# spinac.net
KiCad netlist of a schematic drawn in EAGLE
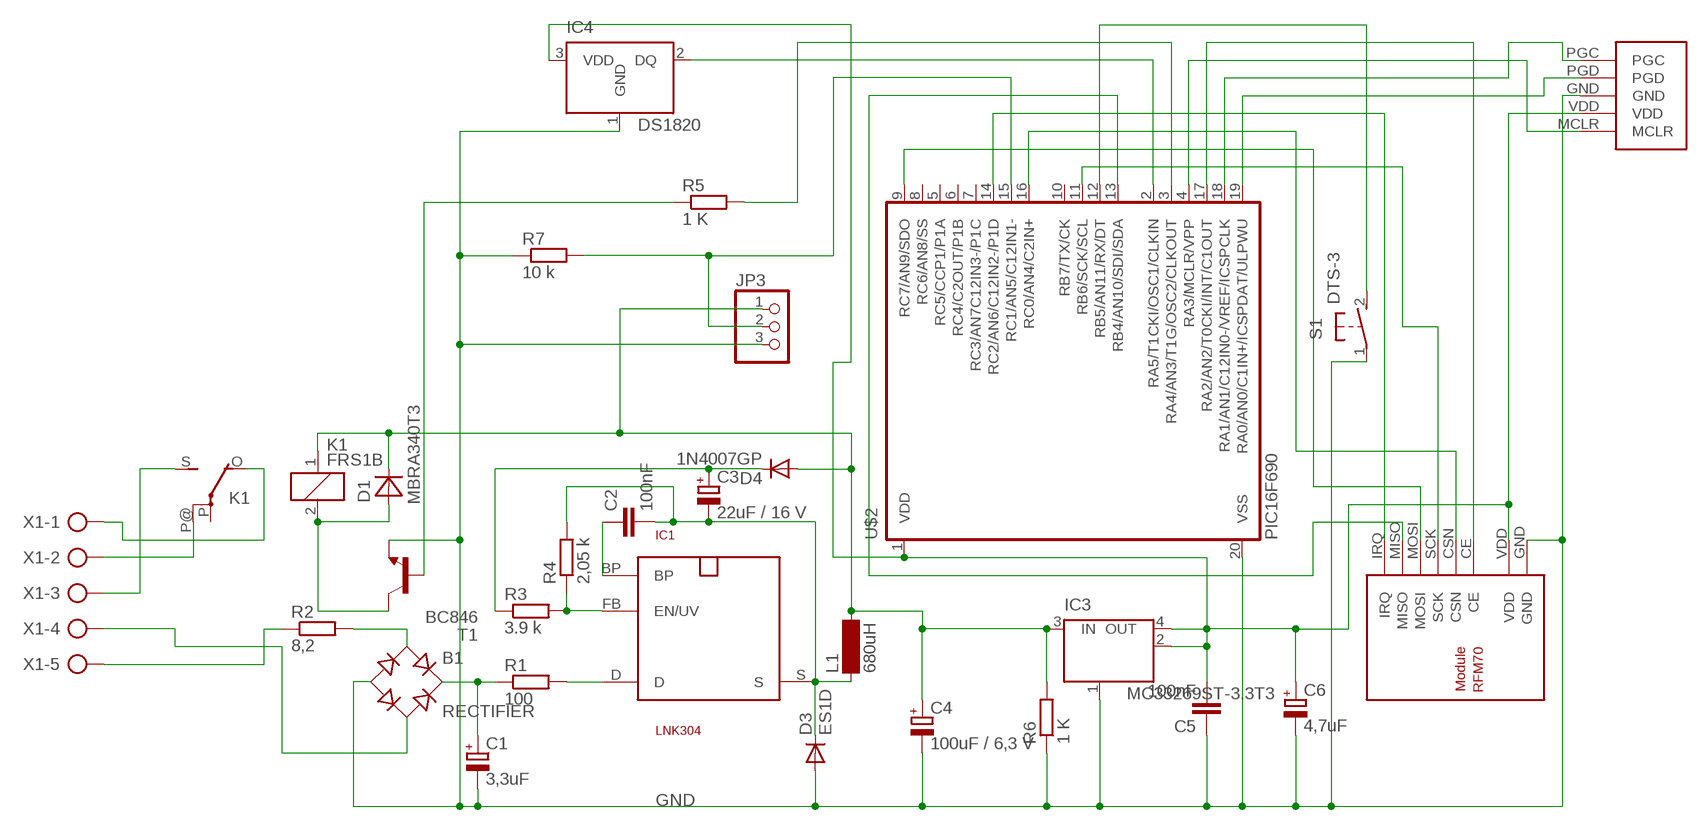
[diagram p0: schematic, sheet 1]

(export (version "E")
  (design (tool "Eeschema 10.0.6"))
  (components
    (comp (ref "B1")
      (value "RECTIFIER")
      (footprint "eagle-import:TO-269AA")
      (libsource (lib "eagle-import") (part "RECTIFIER-S40"))
    )
    (comp (ref "C1")
      (value "3,3uF")
      (footprint "eagle-import:E5-10,5")
      (libsource (lib "eagle-import") (part "CPOL-EUE5-10.5"))
    )
    (comp (ref "C2")
      (value "100nF")
      (footprint "eagle-import:C2012")
      (libsource (lib "eagle-import") (part "C-EUC2012"))
    )
    (comp (ref "C3")
      (value "22uF / 16 V")
      (footprint "eagle-import:SMC_C")
      (libsource (lib "eagle-import") (part "CPOL-EUSMCC"))
    )
    (comp (ref "C4")
      (value "100uF / 6,3 V")
      (footprint "eagle-import:E2,5-5")
      (libsource (lib "eagle-import") (part "CPOL-EUE2.5-5"))
    )
    (comp (ref "C5")
      (value "100nF")
      (footprint "eagle-import:C2012")
      (libsource (lib "eagle-import") (part "C-EUC2012"))
    )
    (comp (ref "C6")
      (value "4,7uF")
      (footprint "eagle-import:SMC_A")
      (libsource (lib "eagle-import") (part "CPOL-EUSMCA"))
    )
    (comp (ref "D1")
      (value "MBRA340T3")
      (footprint "eagle-import:SMA")
      (libsource (lib "eagle-import") (part "MBRA340T3"))
    )
    (comp (ref "D3")
      (value "ES1D")
      (footprint "eagle-import:DO214AC")
      (libsource (lib "eagle-import") (part "DIODE-DO214AC"))
    )
    (comp (ref "D4")
      (value "1N4007GP")
      (footprint "eagle-import:DO214AA")
      (libsource (lib "eagle-import") (part "DIODE-DO214AA"))
    )
    (comp (ref "IC1")
      (value "LNK304")
      (footprint "eagle-import:SO-8C")
      (libsource (lib "eagle-import") (part "SO-8C"))
    )
    (comp (ref "IC3")
      (value "MC33269ST-3.3T3")
      (footprint "eagle-import:SOT223")
      (libsource (lib "eagle-import") (part "MC33269ST-3.3T3"))
    )
    (comp (ref "IC4")
      (value "DS1820")
      (footprint "eagle-import:TO-92")
      (libsource (lib "eagle-import") (part "DS1820"))
    )
    (comp (ref "JP3")
      (value "PINHD-1X3")
      (footprint "eagle-import:1X03")
      (libsource (lib "eagle-import") (part "PINHD-1X3"))
    )
    (comp (ref "K1")
      (value "FRS1B")
      (footprint "eagle-import:FRS1B")
      (libsource (lib "eagle-import") (part "FRS1B"))
    )
    (comp (ref "L1")
      (value "680uH")
      (footprint "eagle-import:BS11")
      (libsource (lib "eagle-import") (part "BS11"))
    )
    (comp (ref "R1")
      (value "100")
      (footprint "eagle-import:R2512W")
      (libsource (lib "eagle-import") (part "R-EU_R2512W"))
    )
    (comp (ref "R2")
      (value "8,2")
      (footprint "eagle-import:0411_12")
      (libsource (lib "eagle-import") (part "R-EU_0411/12"))
    )
    (comp (ref "R3")
      (value "3.9 k")
      (footprint "eagle-import:M2012")
      (libsource (lib "eagle-import") (part "R-EU_M2012"))
    )
    (comp (ref "R4")
      (value "2,05 k")
      (footprint "eagle-import:M2012")
      (libsource (lib "eagle-import") (part "R-EU_M2012"))
    )
    (comp (ref "R5")
      (value "1 K")
      (footprint "eagle-import:M2012")
      (libsource (lib "eagle-import") (part "R-EU_M2012"))
    )
    (comp (ref "R6")
      (value "1 K")
      (footprint "eagle-import:M2012")
      (libsource (lib "eagle-import") (part "R-EU_M2012"))
    )
    (comp (ref "R7")
      (value "10 k")
      (footprint "eagle-import:M2012")
      (libsource (lib "eagle-import") (part "R-EU_M2012"))
    )
    (comp (ref "S1")
      (value "DTS-3")
      (footprint "eagle-import:DTS-3")
      (libsource (lib "eagle-import") (part "DTS-3"))
    )
    (comp (ref "T1")
      (value "BC846")
      (footprint "eagle-import:SOT23")
      (libsource (lib "eagle-import") (part "BC846"))
    )
    (comp (ref "U$1")
      (value "RFM70")
      (footprint "eagle-import:RFM70")
      (libsource (lib "eagle-import") (part "RFM70"))
    )
    (comp (ref "U$2")
      (value "PIC16F690")
      (footprint "eagle-import:SSOP20")
      (libsource (lib "eagle-import") (part "PIC16F690"))
    )
    (comp (ref "U$3")
      (value "PROGRAMMINGHEADERDIP")
      (footprint "eagle-import:PROGHEADER")
      (libsource (lib "eagle-import") (part "PROGRAMMINGHEADERDIP"))
    )
    (comp (ref "X1")
      (value "AK500/5")
      (footprint "eagle-import:AK500_5")
      (libsource (lib "eagle-import") (part "AK500/5"))
    )
  )
  (nets
    (net (code "1") (name "/GND") (class "Default")
      (node (ref "B1") (pin "-") (pinfunction "-_-") (pintype "passive"))
      (node (ref "C1") (pin "-") (pinfunction "-_-") (pintype "passive"))
      (node (ref "C4") (pin "-") (pinfunction "-_-") (pintype "passive"))
      (node (ref "C5") (pin "1") (pinfunction "1_1") (pintype "passive"))
      (node (ref "C6") (pin "-") (pinfunction "-_-") (pintype "passive"))
      (node (ref "D3") (pin "A") (pinfunction "A_A") (pintype "passive"))
      (node (ref "IC3") (pin "1") (pinfunction "GND/ADJ_1") (pintype "input"))
      (node (ref "IC4") (pin "1") (pinfunction "GND_1") (pintype "power_in"))
      (node (ref "JP3") (pin "3") (pinfunction "3_3") (pintype "passive"))
      (node (ref "R6") (pin "1") (pinfunction "1_1") (pintype "passive"))
      (node (ref "R7") (pin "1") (pinfunction "1_1") (pintype "passive"))
      (node (ref "S1") (pin "1") (pinfunction "1_1") (pintype "passive"))
      (node (ref "T1") (pin "2") (pinfunction "E_2") (pintype "passive"))
      (node (ref "U$1") (pin "GND") (pinfunction "GND_GND") (pintype "power_in"))
      (node (ref "U$2") (pin "20") (pinfunction "VSS_20") (pintype "power_in"))
      (node (ref "U$3") (pin "GND") (pinfunction "GND_GND") (pintype "power_in"))
    )
    (net (code "2") (name "Net-(B1-Pad+)") (class "Default")
      (node (ref "B1") (pin "+") (pinfunction "+_+") (pintype "passive"))
      (node (ref "C1") (pin "+") (pinfunction "+_+") (pintype "passive"))
      (node (ref "R1") (pin "1") (pinfunction "1_1") (pintype "passive"))
    )
    (net (code "3") (name "Net-(B1-PadAC1)") (class "Default")
      (node (ref "B1") (pin "AC1") (pinfunction "AC1_AC1") (pintype "passive"))
      (node (ref "R2") (pin "2") (pinfunction "2_2") (pintype "passive"))
    )
    (net (code "4") (name "Net-(C2-Pad1)") (class "Default")
      (node (ref "C2") (pin "1") (pinfunction "1_1") (pintype "passive"))
      (node (ref "IC1") (pin "BP") (pinfunction "BP_BP") (pintype "passive"))
    )
    (net (code "5") (name "Net-(C2-Pad2)") (class "Default")
      (node (ref "C2") (pin "2") (pinfunction "2_2") (pintype "passive"))
      (node (ref "C3") (pin "-") (pinfunction "-_-") (pintype "passive"))
      (node (ref "D3") (pin "C") (pinfunction "C_C") (pintype "passive"))
      (node (ref "IC1") (pin "S") (pinfunction "S_S") (pintype "power_in"))
      (node (ref "L1") (pin "1") (pinfunction "1_1") (pintype "passive"))
      (node (ref "R4") (pin "2") (pinfunction "2_2") (pintype "passive"))
    )
    (net (code "6") (name "Net-(C3-Pad+)") (class "Default")
      (node (ref "C3") (pin "+") (pinfunction "+_+") (pintype "passive"))
      (node (ref "D4") (pin "C") (pinfunction "C_C") (pintype "passive"))
      (node (ref "R3") (pin "1") (pinfunction "1_1") (pintype "passive"))
    )
    (net (code "7") (name "Net-(IC1-EN{slash}UV)") (class "Default")
      (node (ref "IC1") (pin "FB") (pinfunction "EN/UV_FB") (pintype "input"))
      (node (ref "R3") (pin "2") (pinfunction "2_2") (pintype "passive"))
      (node (ref "R4") (pin "1") (pinfunction "1_1") (pintype "passive"))
    )
    (net (code "8") (name "Net-(IC1-PadD)") (class "Default")
      (node (ref "IC1") (pin "D") (pinfunction "D_D") (pintype "open_collector"))
      (node (ref "R1") (pin "2") (pinfunction "2_2") (pintype "passive"))
    )
    (net (code "9") (name "Net-(IC3-IN)") (class "Default")
      (node (ref "C4") (pin "+") (pinfunction "+_+") (pintype "passive"))
      (node (ref "D1") (pin "C") (pinfunction "C_C") (pintype "passive"))
      (node (ref "D4") (pin "A") (pinfunction "A_A") (pintype "passive"))
      (node (ref "IC3") (pin "3") (pinfunction "IN_3") (pintype "input"))
      (node (ref "JP3") (pin "1") (pinfunction "1_1") (pintype "passive"))
      (node (ref "K1") (pin "1") (pinfunction "1_1") (pintype "passive"))
      (node (ref "L1") (pin "2") (pinfunction "2_2") (pintype "passive"))
      (node (ref "R6") (pin "2") (pinfunction "2_2") (pintype "passive"))
    )
    (net (code "10") (name "Net-(IC4-DQ)") (class "Default")
      (node (ref "IC4") (pin "2") (pinfunction "DQ_2") (pintype "output"))
      (node (ref "U$2") (pin "2") (pinfunction "RA5/T1CKI/OSC1/CLKIN_2") (pintype "bidirectional"))
    )
    (net (code "11") (name "Net-(IC4-VDD)") (class "Default")
      (node (ref "C5") (pin "2") (pinfunction "2_2") (pintype "passive"))
      (node (ref "C6") (pin "+") (pinfunction "+_+") (pintype "passive"))
      (node (ref "IC3") (pin "2") (pinfunction "OUT_2") (pintype "passive"))
      (node (ref "IC3") (pin "4") (pinfunction "OUT_4") (pintype "passive"))
      (node (ref "IC4") (pin "3") (pinfunction "VDD_3") (pintype "input"))
      (node (ref "U$1") (pin "VDD") (pinfunction "VDD_VDD") (pintype "power_in"))
      (node (ref "U$2") (pin "1") (pinfunction "VDD_1") (pintype "power_in"))
      (node (ref "U$3") (pin "VDD") (pinfunction "VDD_VDD") (pintype "power_in"))
    )
    (net (code "12") (name "Net-(T1-B)") (class "Default")
      (node (ref "R5") (pin "1") (pinfunction "1_1") (pintype "passive"))
      (node (ref "T1") (pin "1") (pinfunction "B_1") (pintype "passive"))
    )
    (net (code "13") (name "Net-(T1-C)") (class "Default")
      (node (ref "D1") (pin "A") (pinfunction "A_A") (pintype "passive"))
      (node (ref "K1") (pin "2") (pinfunction "2_2") (pintype "passive"))
      (node (ref "T1") (pin "3") (pinfunction "C_3") (pintype "passive"))
    )
    (net (code "14") (name "Net-(U$2-RA0{slash}AN0{slash}C1IN+{slash}ICSPDAT{slash}ULPWU)") (class "Default")
      (node (ref "U$2") (pin "19") (pinfunction "RA0/AN0/C1IN+/ICSPDAT/ULPWU_19") (pintype "bidirectional"))
      (node (ref "U$3") (pin "PGD") (pinfunction "PGD_PGD") (pintype "bidirectional"))
    )
    (net (code "15") (name "Net-(U$2-RA1{slash}AN1{slash}C12IN0-{slash}VREF{slash}ICSPCLK)") (class "Default")
      (node (ref "U$2") (pin "18") (pinfunction "RA1/AN1/C12IN0-/VREF/ICSPCLK_18") (pintype "bidirectional"))
      (node (ref "U$3") (pin "PGC") (pinfunction "PGC_PGC") (pintype "bidirectional"))
    )
    (net (code "16") (name "Net-(U$2-RA2{slash}AN2{slash}T0CKI{slash}INT{slash}C1OUT)") (class "Default")
      (node (ref "U$1") (pin "CE") (pinfunction "CE_CE") (pintype "bidirectional"))
      (node (ref "U$2") (pin "17") (pinfunction "RA2/AN2/T0CKI/INT/C1OUT_17") (pintype "bidirectional"))
    )
    (net (code "17") (name "Net-(U$2-RA3{slash}MCLR{slash}VPP)") (class "Default")
      (node (ref "U$2") (pin "4") (pinfunction "RA3/MCLR/VPP_4") (pintype "bidirectional"))
      (node (ref "U$3") (pin "MCLR") (pinfunction "MCLR_MCLR") (pintype "output"))
    )
    (net (code "18") (name "Net-(U$2-RA4{slash}AN3{slash}T1G{slash}OSC2{slash}CLKOUT)") (class "Default")
      (node (ref "R5") (pin "2") (pinfunction "2_2") (pintype "passive"))
      (node (ref "U$2") (pin "3") (pinfunction "RA4/AN3/T1G/OSC2/CLKOUT_3") (pintype "bidirectional"))
    )
    (net (code "19") (name "Net-(U$2-RB4{slash}AN10{slash}SDI{slash}SDA)") (class "Default")
      (node (ref "U$1") (pin "MISO") (pinfunction "MISO_MISO") (pintype "bidirectional"))
      (node (ref "U$2") (pin "13") (pinfunction "RB4/AN10/SDI/SDA_13") (pintype "bidirectional"))
    )
    (net (code "20") (name "Net-(U$2-RB5{slash}AN11{slash}RX{slash}DT)") (class "Default")
      (node (ref "S1") (pin "2") (pinfunction "2_2") (pintype "passive"))
      (node (ref "U$2") (pin "12") (pinfunction "RB5/AN11/RX/DT_12") (pintype "bidirectional"))
    )
    (net (code "21") (name "Net-(U$2-RB6{slash}SCK{slash}SCL)") (class "Default")
      (node (ref "U$1") (pin "SCK") (pinfunction "SCK_SCK") (pintype "bidirectional"))
      (node (ref "U$2") (pin "11") (pinfunction "RB6/SCK/SCL_11") (pintype "bidirectional"))
    )
    (net (code "22") (name "Net-(U$2-RC0{slash}AN4{slash}C2IN+)") (class "Default")
      (node (ref "U$1") (pin "CSN") (pinfunction "CSN_CSN") (pintype "bidirectional"))
      (node (ref "U$2") (pin "16") (pinfunction "RC0/AN4/C2IN+_16") (pintype "bidirectional"))
    )
    (net (code "23") (name "Net-(U$2-RC1{slash}AN5{slash}C12IN1-)") (class "Default")
      (node (ref "JP3") (pin "2") (pinfunction "2_2") (pintype "passive"))
      (node (ref "R7") (pin "2") (pinfunction "2_2") (pintype "passive"))
      (node (ref "U$2") (pin "15") (pinfunction "RC1/AN5/C12IN1-_15") (pintype "bidirectional"))
    )
    (net (code "24") (name "Net-(U$2-RC2{slash}AN6{slash}C12IN2-{slash}P1D)") (class "Default")
      (node (ref "U$1") (pin "IRQ") (pinfunction "IRQ_IRQ") (pintype "bidirectional"))
      (node (ref "U$2") (pin "14") (pinfunction "RC2/AN6/C12IN2-/P1D_14") (pintype "bidirectional"))
    )
    (net (code "25") (name "Net-(U$2-RC7{slash}AN9{slash}SDO)") (class "Default")
      (node (ref "U$1") (pin "MOSI") (pinfunction "MOSI_MOSI") (pintype "bidirectional"))
      (node (ref "U$2") (pin "9") (pinfunction "RC7/AN9/SDO_9") (pintype "bidirectional"))
    )
    (net (code "26") (name "Net-(X1A-KL)") (class "Default")
      (node (ref "K1") (pin "O") (pinfunction "O_O") (pintype "passive"))
      (node (ref "X1") (pin "1") (pinfunction "KL_1") (pintype "passive"))
    )
    (net (code "27") (name "Net-(X1B-KL)") (class "Default")
      (node (ref "K1") (pin "P@") (pinfunction "P_P@") (pintype "passive"))
      (node (ref "X1") (pin "2") (pinfunction "KL_2") (pintype "passive"))
    )
    (net (code "28") (name "Net-(X1C-KL)") (class "Default")
      (node (ref "K1") (pin "S") (pinfunction "S_S") (pintype "passive"))
      (node (ref "X1") (pin "3") (pinfunction "KL_3") (pintype "passive"))
    )
    (net (code "29") (name "Net-(X1D-KL)") (class "Default")
      (node (ref "B1") (pin "AC2") (pinfunction "AC2_AC2") (pintype "passive"))
      (node (ref "X1") (pin "4") (pinfunction "KL_4") (pintype "passive"))
    )
    (net (code "30") (name "Net-(X1E-KL)") (class "Default")
      (node (ref "R2") (pin "1") (pinfunction "1_1") (pintype "passive"))
      (node (ref "X1") (pin "5") (pinfunction "KL_5") (pintype "passive"))
    )
    (net (code "31") (name "unconnected-(K1-PadP)") (class "Default")
      (node (ref "K1") (pin "P") (pinfunction "P_P") (pintype "passive"))
    )
    (net (code "32") (name "unconnected-(U$2-RB7{slash}TX{slash}CK-Pad10)") (class "Default")
      (node (ref "U$2") (pin "10") (pinfunction "RB7/TX/CK_10") (pintype "bidirectional"))
    )
    (net (code "33") (name "unconnected-(U$2-RC3{slash}AN7C12IN3-{slash}P1C-Pad7)") (class "Default")
      (node (ref "U$2") (pin "7") (pinfunction "RC3/AN7C12IN3-/P1C_7") (pintype "bidirectional"))
    )
    (net (code "34") (name "unconnected-(U$2-RC4{slash}C2OUT{slash}P1B-Pad6)") (class "Default")
      (node (ref "U$2") (pin "6") (pinfunction "RC4/C2OUT/P1B_6") (pintype "bidirectional"))
    )
    (net (code "35") (name "unconnected-(U$2-RC5{slash}CCP1{slash}P1A-Pad5)") (class "Default")
      (node (ref "U$2") (pin "5") (pinfunction "RC5/CCP1/P1A_5") (pintype "bidirectional"))
    )
    (net (code "36") (name "unconnected-(U$2-RC6{slash}AN8{slash}SS-Pad8)") (class "Default")
      (node (ref "U$2") (pin "8") (pinfunction "RC6/AN8/SS_8") (pintype "bidirectional"))
    )
  )
)
